# JTAG_chain_SFPGA_flash.net
KiCad netlist of a schematic drawn in Altium Designer
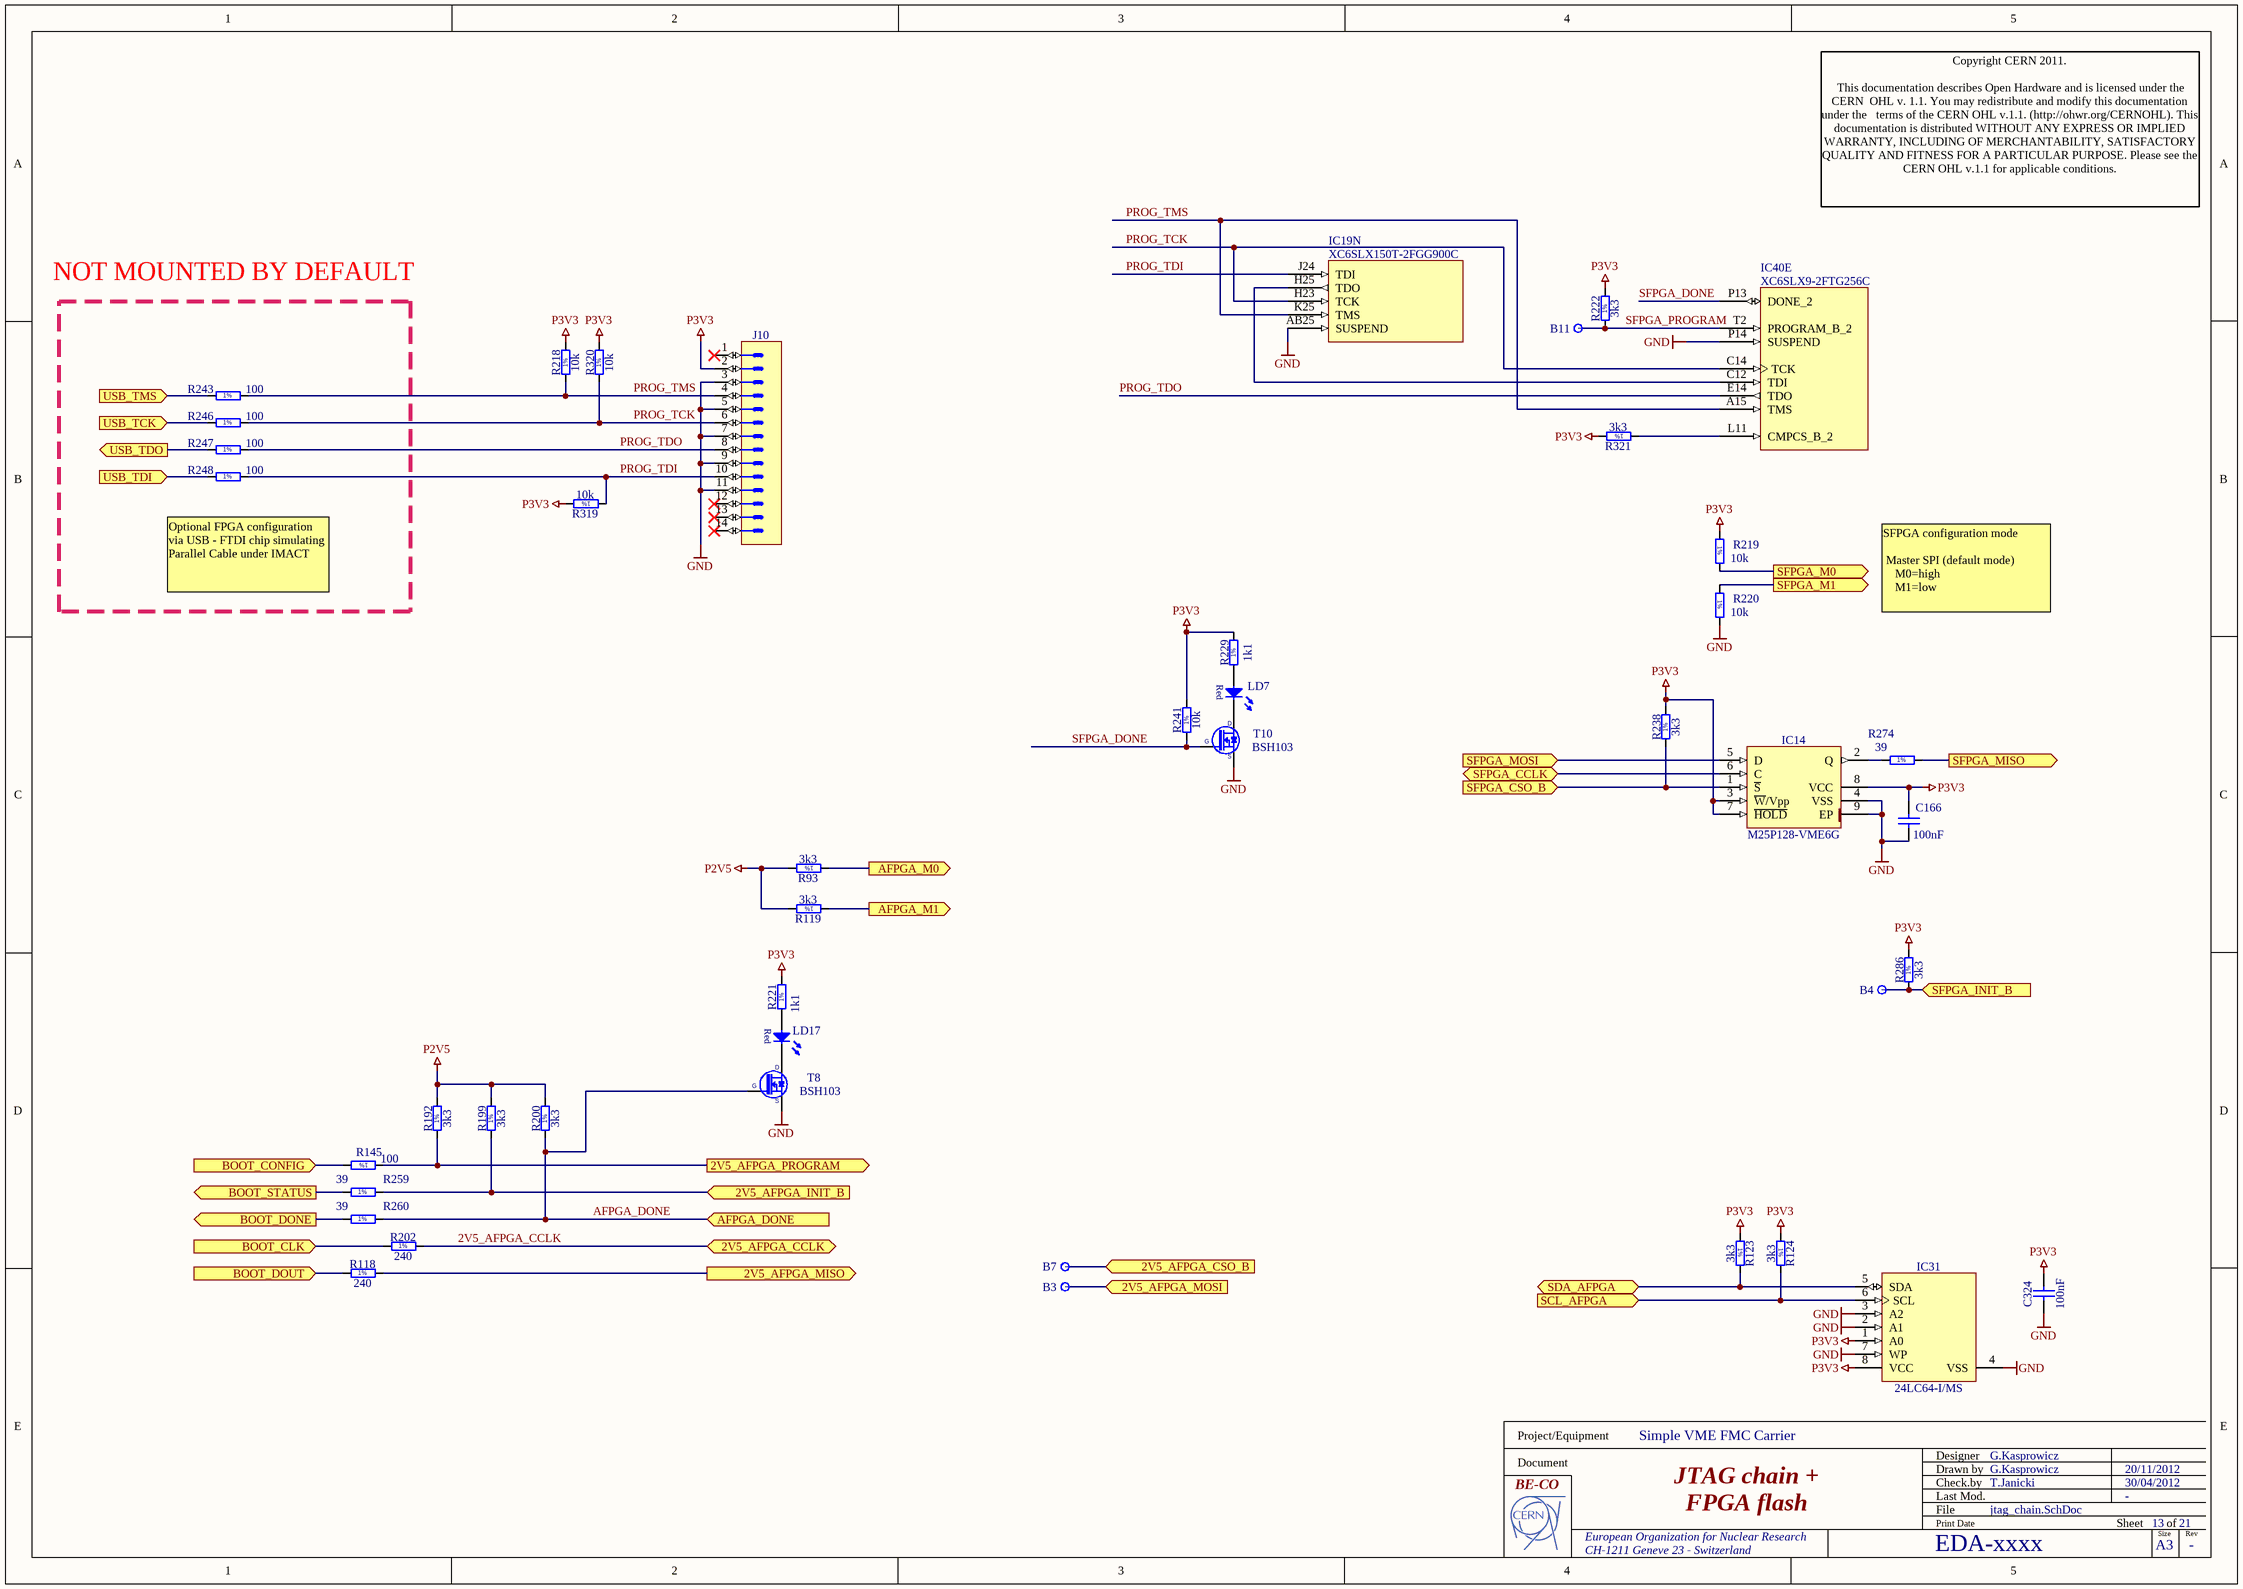
[diagram p0: JTAG chain + SFPGA flash.SchDoc]

(export (version "E")
  (design (tool "Eeschema 10.0.6"))
  (components
    (comp (ref "B3")
      (value "Plated Hole")
      (footprint "c130h80")
      (description "Single Terminal Socket")
      (fields (field (name "PART NUMBER") "PLATED_HOLE0.8_PAD1.3") (field (name "AUTHOR") "CERN DEM JLC"))
      (libsource (lib "Eletro-mechanical") (part "Single Terminal Socket"))
    )
    (comp (ref "B4")
      (value "Plated Hole")
      (footprint "c130h80")
      (description "Single Terminal Socket")
      (fields (field (name "PART NUMBER") "PLATED_HOLE0.8_PAD1.3") (field (name "AUTHOR") "CERN DEM JLC"))
      (libsource (lib "Eletro-mechanical") (part "Single Terminal Socket"))
    )
    (comp (ref "B7")
      (value "Plated Hole")
      (footprint "c130h80")
      (description "Single Terminal Socket")
      (fields (field (name "PART NUMBER") "PLATED_HOLE0.8_PAD1.3") (field (name "AUTHOR") "CERN DEM JLC"))
      (libsource (lib "Eletro-mechanical") (part "Single Terminal Socket"))
    )
    (comp (ref "B11")
      (value "Plated Hole")
      (footprint "c130h80")
      (description "Single Terminal Socket")
      (fields (field (name "PART NUMBER") "PLATED_HOLE0.8_PAD1.3") (field (name "AUTHOR") "CERN DEM JLC"))
      (libsource (lib "Eletro-mechanical") (part "Single Terminal Socket"))
    )
    (comp (ref "C166")
      (value "100nF")
      (footprint "CAPC1005X55N")
      (description "Non-polarised capacitor")
      (fields
        (field (name "PART NUMBER") "CC0402_100NF_16V_10%_X7R")
        (field (name "VOLTAGE") "16V")
        (field (name "AUTHOR") "CERN DEM JLC")
      )
      (libsource (lib "Capacitors") (part "Capacitor - non polarized"))
    )
    (comp (ref "C324")
      (value "100nF")
      (footprint "CAPC1005X55N")
      (description "Non-polarised capacitor")
      (fields
        (field (name "PART NUMBER") "CC0402_100NF_16V_10%_X7R")
        (field (name "VOLTAGE") "16V")
        (field (name "AUTHOR") "CERN DEM JLC")
      )
      (libsource (lib "Capacitors") (part "Capacitor - non polarized"))
    )
    (comp (ref "IC14")
      (value "M25P128-VME6G")
      (footprint "PSON127P800X600X100-9N-R640X480")
      (description "128 Mbit (Multilevel), low-voltage, Serial Flash memory with 50-MHz SPI bus interface")
      (fields (field (name "MANUFACTURER") "NUMONYX") (field (name "AUTHOR") "CERN DEM JLC"))
      (libsource (lib "ICs And Semiconductors") (part "M25P128-VME"))
    )
    (comp (ref "IC19")
      (value "XC6SLX150T-2FGG900C")
      (footprint "BGA900C100P30X30_3100X3100X260")
      (description "SPARTAN-6, FPGA, 900-Ball BGA, Commercial Grade, Pb-Free")
      (fields (field (name "MANUFACTURER") "XILINX") (field (name "AUTHOR") "CERN DEM JLC"))
      (libsource (lib "ICs And Semiconductors") (part "XC6SLX150T-2FGG900C"))
    )
    (comp (ref "IC31")
      (value "24LC64-I/MS")
      (footprint "SOP65P490X110-8N")
      (description "64K I2C Serial EEPROM")
      (fields (field (name "MANUFACTURER") "MICROCHIP TECHNOLOGY") (field (name "AUTHOR") "CERN DEM JLC"))
      (libsource (lib "ICs And Semiconductors") (part "24LC64-I/MS"))
    )
    (comp (ref "IC40")
      (value "XC6SLX9-2FTG256C")
      (footprint "BGA256C100P16X16_1700X1700X155")
      (fields (field (name "MANUFACTURER") "XILINX") (field (name "AUTHOR") "CERN DEM JLC"))
      (libsource (lib "ICs And Semiconductors") (part "XC6SLX9-2FTG256C"))
    )
    (comp (ref "J10")
      (value "Milli-Grid")
      (footprint "MOLEX_87832-1420")
      (description "Connector 14 Male")
      (fields
        (field (name "PART NUMBER") "MOLEX_87832-1420")
        (field (name "MANUFACTURER") "MOLEX")
        (field (name "AUTHOR") "CERN DEM JLC")
      )
      (libsource (lib "Connectors") (part "Connector 14 Male"))
    )
    (comp (ref "LD7")
      (value "Red")
      (footprint "LEDC1608X80N_RED")
      (description "LED Red 1C 2A")
      (fields
        (field (name "PART NUMBER") "LED_ROHM_SML-311UTT86K")
        (field (name "MANUFACTURER") "ROHM")
        (field (name "AUTHOR") "CERN DEM JLC")
      )
      (libsource (lib "ICs And Semiconductors") (part "LED Red 1C 2A"))
    )
    (comp (ref "LD17")
      (value "Red")
      (footprint "LEDC1608X80N_RED")
      (description "LED Red 1C 2A")
      (fields
        (field (name "PART NUMBER") "LED_ROHM_SML-311UTT86K")
        (field (name "MANUFACTURER") "ROHM")
        (field (name "AUTHOR") "CERN DEM JLC")
      )
      (libsource (lib "ICs And Semiconductors") (part "LED Red 1C 2A"))
    )
    (comp (ref "R93")
      (value "3k3")
      (footprint "RESC1608X55N")
      (description "Resistor - 1%")
      (fields
        (field (name "PART NUMBER") "R0603_3K3_1%_0.1W_100PPM")
        (field (name "POWER") "0.1W")
        (field (name "AUTHOR") "CERN DEM JLC")
      )
      (libsource (lib "Resistors") (part "Resistor - 1%"))
    )
    (comp (ref "R118")
      (value "240")
      (footprint "RESC1608X55N")
      (description "Resistor - 1%")
      (fields
        (field (name "PART NUMBER") "R0603_240R_1%_0.1W_100PPM")
        (field (name "POWER") "0.1W")
        (field (name "AUTHOR") "CERN DEM JLC")
      )
      (libsource (lib "Resistors") (part "Resistor - 1%"))
    )
    (comp (ref "R119")
      (value "3k3")
      (footprint "RESC1608X55N")
      (description "Resistor - 1%")
      (fields
        (field (name "PART NUMBER") "R0603_3K3_1%_0.1W_100PPM")
        (field (name "POWER") "0.1W")
        (field (name "AUTHOR") "CERN DEM JLC")
      )
      (libsource (lib "Resistors") (part "Resistor - 1%"))
    )
    (comp (ref "R123")
      (value "3k3")
      (footprint "RESC1608X55N")
      (description "Resistor - 1%")
      (fields
        (field (name "PART NUMBER") "R0603_3K3_1%_0.1W_100PPM")
        (field (name "POWER") "0.1W")
        (field (name "AUTHOR") "CERN DEM JLC")
      )
      (libsource (lib "Resistors") (part "Resistor - 1%"))
    )
    (comp (ref "R124")
      (value "3k3")
      (footprint "RESC1608X55N")
      (description "Resistor - 1%")
      (fields
        (field (name "PART NUMBER") "R0603_3K3_1%_0.1W_100PPM")
        (field (name "POWER") "0.1W")
        (field (name "AUTHOR") "CERN DEM JLC")
      )
      (libsource (lib "Resistors") (part "Resistor - 1%"))
    )
    (comp (ref "R145")
      (value "100")
      (footprint "RESC1608X55N")
      (description "Resistor - 1%")
      (fields
        (field (name "PART NUMBER") "R0603_100R_1%_0.1W_100PPM")
        (field (name "POWER") "0.1W")
        (field (name "AUTHOR") "CERN DEM JLC")
      )
      (libsource (lib "Resistors") (part "Resistor - 1%"))
    )
    (comp (ref "R192")
      (value "3k3")
      (footprint "RESC1608X55N")
      (description "Resistor - 1%")
      (fields
        (field (name "PART NUMBER") "R0603_3K3_1%_0.1W_100PPM")
        (field (name "POWER") "0.1W")
        (field (name "AUTHOR") "CERN DEM JLC")
      )
      (libsource (lib "Resistors") (part "Resistor - 1%"))
    )
    (comp (ref "R199")
      (value "3k3")
      (footprint "RESC1608X55N")
      (description "Resistor - 1%")
      (fields
        (field (name "PART NUMBER") "R0603_3K3_1%_0.1W_100PPM")
        (field (name "POWER") "0.1W")
        (field (name "AUTHOR") "CERN DEM JLC")
      )
      (libsource (lib "Resistors") (part "Resistor - 1%"))
    )
    (comp (ref "R200")
      (value "3k3")
      (footprint "RESC1608X55N")
      (description "Resistor - 1%")
      (fields
        (field (name "PART NUMBER") "R0603_3K3_1%_0.1W_100PPM")
        (field (name "POWER") "0.1W")
        (field (name "AUTHOR") "CERN DEM JLC")
      )
      (libsource (lib "Resistors") (part "Resistor - 1%"))
    )
    (comp (ref "R202")
      (value "240")
      (footprint "RESC1608X55N")
      (description "Resistor - 1%")
      (fields
        (field (name "PART NUMBER") "R0603_240R_1%_0.1W_100PPM")
        (field (name "POWER") "0.1W")
        (field (name "AUTHOR") "CERN DEM JLC")
      )
      (libsource (lib "Resistors") (part "Resistor - 1%"))
    )
    (comp (ref "R218")
      (value "10k")
      (footprint "RESC1608X55N")
      (description "Resistor - 1%")
      (fields
        (field (name "PART NUMBER") "R0603_10K_1%_0.1W_100PPM")
        (field (name "POWER") "0.1W")
        (field (name "AUTHOR") "CERN DEM JLC")
      )
      (libsource (lib "Resistors") (part "Resistor - 1%"))
    )
    (comp (ref "R219")
      (value "10k")
      (footprint "RESC1608X55N")
      (description "Resistor - 1%")
      (fields
        (field (name "PART NUMBER") "R0603_10K_1%_0.1W_100PPM")
        (field (name "POWER") "0.1W")
        (field (name "AUTHOR") "CERN DEM JLC")
      )
      (libsource (lib "Resistors") (part "Resistor - 1%"))
    )
    (comp (ref "R220")
      (value "10k")
      (footprint "RESC1608X55N")
      (description "Resistor - 1%")
      (fields
        (field (name "PART NUMBER") "R0603_10K_1%_0.1W_100PPM")
        (field (name "POWER") "0.1W")
        (field (name "AUTHOR") "CERN DEM JLC")
      )
      (libsource (lib "Resistors") (part "Resistor - 1%"))
    )
    (comp (ref "R221")
      (value "1k1")
      (footprint "RESC1608X55N")
      (description "Resistor - 1%")
      (fields
        (field (name "PART NUMBER") "R0603_1K1_1%_0.1W_100PPM")
        (field (name "POWER") "0.1W")
        (field (name "AUTHOR") "CERN DEM JLC")
      )
      (libsource (lib "Resistors") (part "Resistor - 1%"))
    )
    (comp (ref "R222")
      (value "3k3")
      (footprint "RESC1608X55N")
      (description "Resistor - 1%")
      (fields
        (field (name "PART NUMBER") "R0603_3K3_1%_0.1W_100PPM")
        (field (name "POWER") "0.1W")
        (field (name "AUTHOR") "CERN DEM JLC")
      )
      (libsource (lib "Resistors") (part "Resistor - 1%"))
    )
    (comp (ref "R229")
      (value "1k1")
      (footprint "RESC1608X55N")
      (description "Resistor - 1%")
      (fields
        (field (name "PART NUMBER") "R0603_1K1_1%_0.1W_100PPM")
        (field (name "POWER") "0.1W")
        (field (name "AUTHOR") "CERN DEM JLC")
      )
      (libsource (lib "Resistors") (part "Resistor - 1%"))
    )
    (comp (ref "R238")
      (value "3k3")
      (footprint "RESC1608X55N")
      (description "Resistor - 1%")
      (fields
        (field (name "PART NUMBER") "R0603_3K3_1%_0.1W_100PPM")
        (field (name "POWER") "0.1W")
        (field (name "AUTHOR") "CERN DEM JLC")
      )
      (libsource (lib "Resistors") (part "Resistor - 1%"))
    )
    (comp (ref "R241")
      (value "10k")
      (footprint "RESC1608X55N")
      (description "Resistor - 1%")
      (fields
        (field (name "PART NUMBER") "R0603_10K_1%_0.1W_100PPM")
        (field (name "POWER") "0.1W")
        (field (name "AUTHOR") "CERN DEM JLC")
      )
      (libsource (lib "Resistors") (part "Resistor - 1%"))
    )
    (comp (ref "R243")
      (value "100")
      (footprint "RESC1608X55N")
      (description "Resistor - 1%")
      (fields
        (field (name "PART NUMBER") "R0603_100R_1%_0.1W_100PPM")
        (field (name "POWER") "0.1W")
        (field (name "AUTHOR") "CERN DEM JLC")
      )
      (libsource (lib "Resistors") (part "Resistor - 1%"))
    )
    (comp (ref "R246")
      (value "100")
      (footprint "RESC1608X55N")
      (description "Resistor - 1%")
      (fields
        (field (name "PART NUMBER") "R0603_100R_1%_0.1W_100PPM")
        (field (name "POWER") "0.1W")
        (field (name "AUTHOR") "CERN DEM JLC")
      )
      (libsource (lib "Resistors") (part "Resistor - 1%"))
    )
    (comp (ref "R247")
      (value "100")
      (footprint "RESC1608X55N")
      (description "Resistor - 1%")
      (fields
        (field (name "PART NUMBER") "R0603_100R_1%_0.1W_100PPM")
        (field (name "POWER") "0.1W")
        (field (name "AUTHOR") "CERN DEM JLC")
      )
      (libsource (lib "Resistors") (part "Resistor - 1%"))
    )
    (comp (ref "R248")
      (value "100")
      (footprint "RESC1608X55N")
      (description "Resistor - 1%")
      (fields
        (field (name "PART NUMBER") "R0603_100R_1%_0.1W_100PPM")
        (field (name "POWER") "0.1W")
        (field (name "AUTHOR") "CERN DEM JLC")
      )
      (libsource (lib "Resistors") (part "Resistor - 1%"))
    )
    (comp (ref "R259")
      (value "39")
      (footprint "RESC1608X55N")
      (description "Resistor - 1%")
      (fields
        (field (name "PART NUMBER") "R0603_39R_1%_0.1W_100PPM")
        (field (name "POWER") "0.1W")
        (field (name "AUTHOR") "CERN DEM JLC")
      )
      (libsource (lib "Resistors") (part "Resistor - 1%"))
    )
    (comp (ref "R260")
      (value "39")
      (footprint "RESC1608X55N")
      (description "Resistor - 1%")
      (fields
        (field (name "PART NUMBER") "R0603_39R_1%_0.1W_100PPM")
        (field (name "POWER") "0.1W")
        (field (name "AUTHOR") "CERN DEM JLC")
      )
      (libsource (lib "Resistors") (part "Resistor - 1%"))
    )
    (comp (ref "R274")
      (value "39")
      (footprint "RESC1608X55N")
      (description "Resistor - 1%")
      (fields
        (field (name "PART NUMBER") "R0603_39R_1%_0.1W_100PPM")
        (field (name "POWER") "0.1W")
        (field (name "AUTHOR") "CERN DEM JLC")
      )
      (libsource (lib "Resistors") (part "Resistor - 1%"))
    )
    (comp (ref "R286")
      (value "3k3")
      (footprint "RESC1608X55N")
      (description "Resistor - 1%")
      (fields
        (field (name "PART NUMBER") "R0603_3K3_1%_0.1W_100PPM")
        (field (name "POWER") "0.1W")
        (field (name "AUTHOR") "CERN DEM JLC")
      )
      (libsource (lib "Resistors") (part "Resistor - 1%"))
    )
    (comp (ref "R319")
      (value "10k")
      (footprint "RESC1608X55N")
      (description "Resistor - 1%")
      (fields
        (field (name "PART NUMBER") "R0603_10K_1%_0.1W_100PPM")
        (field (name "POWER") "0.1W")
        (field (name "AUTHOR") "CERN DEM JLC")
      )
      (libsource (lib "Resistors") (part "Resistor - 1%"))
    )
    (comp (ref "R320")
      (value "10k")
      (footprint "RESC1608X55N")
      (description "Resistor - 1%")
      (fields
        (field (name "PART NUMBER") "R0603_10K_1%_0.1W_100PPM")
        (field (name "POWER") "0.1W")
        (field (name "AUTHOR") "CERN DEM JLC")
      )
      (libsource (lib "Resistors") (part "Resistor - 1%"))
    )
    (comp (ref "R321")
      (value "3k3")
      (footprint "RESC1608X55N")
      (description "Resistor - 1%")
      (fields
        (field (name "PART NUMBER") "R0603_3K3_1%_0.1W_100PPM")
        (field (name "POWER") "0.1W")
        (field (name "AUTHOR") "CERN DEM JLC")
      )
      (libsource (lib "Resistors") (part "Resistor - 1%"))
    )
    (comp (ref "T8")
      (value "BSH103")
      (footprint "SOT95P230X110-3N")
      (description "N-CHANNEL MOSFET WITH DIODE")
      (fields (field (name "MANUFACTURER") "NXP SEMICONDUCTORS") (field (name "AUTHOR") "CERN DEM JLC"))
      (libsource (lib "ICs And Semiconductors") (part "N-MOSFET-D 1G 2S 3D"))
    )
    (comp (ref "T10")
      (value "BSH103")
      (footprint "SOT95P230X110-3N")
      (description "N-CHANNEL MOSFET WITH DIODE")
      (fields (field (name "MANUFACTURER") "NXP SEMICONDUCTORS") (field (name "AUTHOR") "CERN DEM JLC"))
      (libsource (lib "ICs And Semiconductors") (part "N-MOSFET-D 1G 2S 3D"))
    )
  )
  (nets
    (net (code "1") (name "/2V5_AFPGA_CCLK") (class "Default")
      (node (ref "R202") (pin "2") (pinfunction "2_2") (pintype "passive"))
    )
    (net (code "2") (name "/2V5_AFPGA_CSO_B") (class "Default")
      (node (ref "B7") (pin "1") (pinfunction "1_1") (pintype "bidirectional"))
    )
    (net (code "3") (name "/2V5_AFPGA_INIT_B") (class "Default")
      (node (ref "R199") (pin "1") (pinfunction "1_1") (pintype "passive"))
      (node (ref "R259") (pin "2") (pinfunction "2_2") (pintype "passive"))
    )
    (net (code "4") (name "/2V5_AFPGA_MISO") (class "Default")
      (node (ref "R118") (pin "2") (pinfunction "2_2") (pintype "passive"))
    )
    (net (code "5") (name "/2V5_AFPGA_MOSI") (class "Default")
      (node (ref "B3") (pin "1") (pinfunction "1_1") (pintype "bidirectional"))
    )
    (net (code "6") (name "/2V5_AFPGA_PROGRAM") (class "Default")
      (node (ref "R145") (pin "1") (pinfunction "1_1") (pintype "passive"))
      (node (ref "R192") (pin "1") (pinfunction "1_1") (pintype "passive"))
    )
    (net (code "7") (name "/AFPGA_DONE") (class "Default")
      (node (ref "R200") (pin "1") (pinfunction "1_1") (pintype "passive"))
      (node (ref "R260") (pin "2") (pinfunction "2_2") (pintype "passive"))
      (node (ref "T8") (pin "1") (pinfunction "G_1") (pintype "passive"))
    )
    (net (code "8") (name "/AFPGA_M0") (class "Default")
      (node (ref "R93") (pin "1") (pinfunction "1_1") (pintype "passive"))
    )
    (net (code "9") (name "/AFPGA_M1") (class "Default")
      (node (ref "R119") (pin "1") (pinfunction "1_1") (pintype "passive"))
    )
    (net (code "10") (name "/BOOT_CLK") (class "Default")
      (node (ref "R202") (pin "1") (pinfunction "1_1") (pintype "passive"))
    )
    (net (code "11") (name "/BOOT_CONFIG") (class "Default")
      (node (ref "R145") (pin "2") (pinfunction "2_2") (pintype "passive"))
    )
    (net (code "12") (name "/BOOT_DONE") (class "Default")
      (node (ref "R260") (pin "1") (pinfunction "1_1") (pintype "passive"))
    )
    (net (code "13") (name "/BOOT_DOUT") (class "Default")
      (node (ref "R118") (pin "1") (pinfunction "1_1") (pintype "passive"))
    )
    (net (code "14") (name "/BOOT_STATUS") (class "Default")
      (node (ref "R259") (pin "1") (pinfunction "1_1") (pintype "passive"))
    )
    (net (code "15") (name "/PROG_TCK") (class "Default")
      (node (ref "IC19") (pin "H23") (pinfunction "TCK_H23") (pintype "input"))
      (node (ref "IC40") (pin "C14") (pinfunction "TCK_C14") (pintype "input"))
      (node (ref "J10") (pin "6") (pinfunction "6_6") (pintype "bidirectional"))
      (node (ref "R246") (pin "2") (pinfunction "2_2") (pintype "passive"))
      (node (ref "R320") (pin "1") (pinfunction "1_1") (pintype "passive"))
    )
    (net (code "16") (name "/PROG_TDI") (class "Default")
      (node (ref "IC19") (pin "J24") (pinfunction "TDI_J24") (pintype "input"))
      (node (ref "J10") (pin "10") (pinfunction "10_10") (pintype "bidirectional"))
      (node (ref "R248") (pin "2") (pinfunction "2_2") (pintype "passive"))
      (node (ref "R319") (pin "1") (pinfunction "1_1") (pintype "passive"))
    )
    (net (code "17") (name "/PROG_TDO") (class "Default")
      (node (ref "IC40") (pin "E14") (pinfunction "TDO_E14") (pintype "output"))
      (node (ref "J10") (pin "8") (pinfunction "8_8") (pintype "bidirectional"))
      (node (ref "R247") (pin "2") (pinfunction "2_2") (pintype "passive"))
    )
    (net (code "18") (name "/PROG_TMS") (class "Default")
      (node (ref "IC19") (pin "K25") (pinfunction "TMS_K25") (pintype "input"))
      (node (ref "IC40") (pin "A15") (pinfunction "TMS_A15") (pintype "input"))
      (node (ref "J10") (pin "4") (pinfunction "4_4") (pintype "bidirectional"))
      (node (ref "R218") (pin "1") (pinfunction "1_1") (pintype "passive"))
      (node (ref "R243") (pin "2") (pinfunction "2_2") (pintype "passive"))
    )
    (net (code "19") (name "/SCL_AFPGA") (class "Default")
      (node (ref "IC31") (pin "6") (pinfunction "SCL_6") (pintype "input"))
      (node (ref "R124") (pin "2") (pinfunction "2_2") (pintype "passive"))
    )
    (net (code "20") (name "/SDA_AFPGA") (class "Default")
      (node (ref "IC31") (pin "5") (pinfunction "SDA_5") (pintype "bidirectional"))
      (node (ref "R123") (pin "2") (pinfunction "2_2") (pintype "passive"))
    )
    (net (code "21") (name "/SFPGA_CCLK") (class "Default")
      (node (ref "IC14") (pin "6") (pinfunction "C_6") (pintype "input"))
    )
    (net (code "22") (name "/SFPGA_CSO_B") (class "Default")
      (node (ref "IC14") (pin "1") (pinfunction "~{S}_1") (pintype "input"))
      (node (ref "R238") (pin "1") (pinfunction "1_1") (pintype "passive"))
    )
    (net (code "23") (name "/SFPGA_DONE") (class "Default")
      (node (ref "IC40") (pin "P13") (pinfunction "DONE_2_P13") (pintype "bidirectional"))
      (node (ref "R241") (pin "1") (pinfunction "1_1") (pintype "passive"))
      (node (ref "T10") (pin "1") (pinfunction "G_1") (pintype "passive"))
    )
    (net (code "24") (name "/SFPGA_INIT_B") (class "Default")
      (node (ref "B4") (pin "1") (pinfunction "1_1") (pintype "bidirectional"))
      (node (ref "R286") (pin "1") (pinfunction "1_1") (pintype "passive"))
    )
    (net (code "25") (name "/SFPGA_M0") (class "Default")
      (node (ref "R219") (pin "2") (pinfunction "2_2") (pintype "passive"))
    )
    (net (code "26") (name "/SFPGA_M1") (class "Default")
      (node (ref "R220") (pin "1") (pinfunction "1_1") (pintype "passive"))
    )
    (net (code "27") (name "/SFPGA_MISO") (class "Default")
      (node (ref "R274") (pin "2") (pinfunction "2_2") (pintype "passive"))
    )
    (net (code "28") (name "/SFPGA_MOSI") (class "Default")
      (node (ref "IC14") (pin "5") (pinfunction "D_5") (pintype "input"))
    )
    (net (code "29") (name "/SFPGA_PROGRAM") (class "Default")
      (node (ref "B11") (pin "1") (pinfunction "1_1") (pintype "bidirectional"))
      (node (ref "IC40") (pin "T2") (pinfunction "PROGRAM_B_2_T2") (pintype "input"))
      (node (ref "R222") (pin "1") (pinfunction "1_1") (pintype "passive"))
    )
    (net (code "30") (name "/USB_TCK") (class "Default")
      (node (ref "R246") (pin "1") (pinfunction "1_1") (pintype "passive"))
    )
    (net (code "31") (name "/USB_TDI") (class "Default")
      (node (ref "R248") (pin "1") (pinfunction "1_1") (pintype "passive"))
    )
    (net (code "32") (name "/USB_TDO") (class "Default")
      (node (ref "R247") (pin "1") (pinfunction "1_1") (pintype "passive"))
    )
    (net (code "33") (name "/USB_TMS") (class "Default")
      (node (ref "R243") (pin "1") (pinfunction "1_1") (pintype "passive"))
    )
    (net (code "34") (name "GND") (class "Default")
      (node (ref "C166") (pin "2") (pinfunction "2_2") (pintype "passive"))
      (node (ref "C324") (pin "2") (pinfunction "2_2") (pintype "passive"))
      (node (ref "IC14") (pin "4") (pinfunction "VSS_4") (pintype "power_in"))
      (node (ref "IC14") (pin "9") (pinfunction "EP_9") (pintype "power_in"))
      (node (ref "IC19") (pin "AB25") (pinfunction "SUSPEND_AB25") (pintype "input"))
      (node (ref "IC31") (pin "2") (pinfunction "A1_2") (pintype "input"))
      (node (ref "IC31") (pin "3") (pinfunction "A2_3") (pintype "input"))
      (node (ref "IC31") (pin "4") (pinfunction "VSS_4") (pintype "power_in"))
      (node (ref "IC31") (pin "7") (pinfunction "WP_7") (pintype "input"))
      (node (ref "IC40") (pin "P14") (pinfunction "SUSPEND_P14") (pintype "input"))
      (node (ref "J10") (pin "11") (pinfunction "11_11") (pintype "bidirectional"))
      (node (ref "J10") (pin "3") (pinfunction "3_3") (pintype "bidirectional"))
      (node (ref "J10") (pin "5") (pinfunction "5_5") (pintype "bidirectional"))
      (node (ref "J10") (pin "7") (pinfunction "7_7") (pintype "bidirectional"))
      (node (ref "J10") (pin "9") (pinfunction "9_9") (pintype "bidirectional"))
      (node (ref "R220") (pin "2") (pinfunction "2_2") (pintype "passive"))
      (node (ref "T10") (pin "2") (pinfunction "S_2") (pintype "passive"))
      (node (ref "T8") (pin "2") (pinfunction "S_2") (pintype "passive"))
    )
    (net (code "35") (name "Net-(IC14-Q)") (class "Default")
      (node (ref "IC14") (pin "2") (pinfunction "Q_2") (pintype "output"))
      (node (ref "R274") (pin "1") (pinfunction "1_1") (pintype "passive"))
    )
    (net (code "36") (name "Net-(IC19N-TDO)") (class "Default")
      (node (ref "IC19") (pin "H25") (pinfunction "TDO_H25") (pintype "output"))
      (node (ref "IC40") (pin "C12") (pinfunction "TDI_C12") (pintype "input"))
    )
    (net (code "37") (name "Net-(IC40E-CMPCS_B_2)") (class "Default")
      (node (ref "IC40") (pin "L11") (pinfunction "CMPCS_B_2_L11") (pintype "input"))
      (node (ref "R321") (pin "1") (pinfunction "1_1") (pintype "passive"))
    )
    (net (code "38") (name "Net-(LD7-A)") (class "Default")
      (node (ref "LD7") (pin "2") (pinfunction "A_2") (pintype "passive"))
      (node (ref "R229") (pin "1") (pinfunction "1_1") (pintype "passive"))
    )
    (net (code "39") (name "Net-(LD7-C)") (class "Default")
      (node (ref "LD7") (pin "1") (pinfunction "C_1") (pintype "passive"))
      (node (ref "T10") (pin "3") (pinfunction "D_3") (pintype "passive"))
    )
    (net (code "40") (name "Net-(LD17-A)") (class "Default")
      (node (ref "LD17") (pin "2") (pinfunction "A_2") (pintype "passive"))
      (node (ref "R221") (pin "1") (pinfunction "1_1") (pintype "passive"))
    )
    (net (code "41") (name "Net-(LD17-C)") (class "Default")
      (node (ref "LD17") (pin "1") (pinfunction "C_1") (pintype "passive"))
      (node (ref "T8") (pin "3") (pinfunction "D_3") (pintype "passive"))
    )
    (net (code "42") (name "P2V5") (class "Default")
      (node (ref "R119") (pin "2") (pinfunction "2_2") (pintype "passive"))
      (node (ref "R192") (pin "2") (pinfunction "2_2") (pintype "passive"))
      (node (ref "R199") (pin "2") (pinfunction "2_2") (pintype "passive"))
      (node (ref "R200") (pin "2") (pinfunction "2_2") (pintype "passive"))
      (node (ref "R93") (pin "2") (pinfunction "2_2") (pintype "passive"))
    )
    (net (code "43") (name "P3V3") (class "Default")
      (node (ref "C166") (pin "1") (pinfunction "1_1") (pintype "passive"))
      (node (ref "C324") (pin "1") (pinfunction "1_1") (pintype "passive"))
      (node (ref "IC14") (pin "3") (pinfunction "~{W}/Vpp_3") (pintype "input"))
      (node (ref "IC14") (pin "7") (pinfunction "~{HOLD}_7") (pintype "input"))
      (node (ref "IC14") (pin "8") (pinfunction "VCC_8") (pintype "power_in"))
      (node (ref "IC31") (pin "1") (pinfunction "A0_1") (pintype "input"))
      (node (ref "IC31") (pin "8") (pinfunction "VCC_8") (pintype "power_in"))
      (node (ref "J10") (pin "2") (pinfunction "2_2") (pintype "bidirectional"))
      (node (ref "R123") (pin "1") (pinfunction "1_1") (pintype "passive"))
      (node (ref "R124") (pin "1") (pinfunction "1_1") (pintype "passive"))
      (node (ref "R218") (pin "2") (pinfunction "2_2") (pintype "passive"))
      (node (ref "R219") (pin "1") (pinfunction "1_1") (pintype "passive"))
      (node (ref "R221") (pin "2") (pinfunction "2_2") (pintype "passive"))
      (node (ref "R222") (pin "2") (pinfunction "2_2") (pintype "passive"))
      (node (ref "R229") (pin "2") (pinfunction "2_2") (pintype "passive"))
      (node (ref "R238") (pin "2") (pinfunction "2_2") (pintype "passive"))
      (node (ref "R241") (pin "2") (pinfunction "2_2") (pintype "passive"))
      (node (ref "R286") (pin "2") (pinfunction "2_2") (pintype "passive"))
      (node (ref "R319") (pin "2") (pinfunction "2_2") (pintype "passive"))
      (node (ref "R320") (pin "2") (pinfunction "2_2") (pintype "passive"))
      (node (ref "R321") (pin "2") (pinfunction "2_2") (pintype "passive"))
    )
    (net (code "44") (name "unconnected-(J10-Pad1)") (class "Default")
      (node (ref "J10") (pin "1") (pinfunction "1_1") (pintype "bidirectional+no_connect"))
    )
    (net (code "45") (name "unconnected-(J10-Pad12)") (class "Default")
      (node (ref "J10") (pin "12") (pinfunction "12_12") (pintype "bidirectional+no_connect"))
    )
    (net (code "46") (name "unconnected-(J10-Pad13)") (class "Default")
      (node (ref "J10") (pin "13") (pinfunction "13_13") (pintype "bidirectional+no_connect"))
    )
    (net (code "47") (name "unconnected-(J10-Pad14)") (class "Default")
      (node (ref "J10") (pin "14") (pinfunction "14_14") (pintype "bidirectional+no_connect"))
    )
  )
)
